# ADCMP607-step-gen-v2.net
KiCad netlist of a schematic drawn in EAGLE
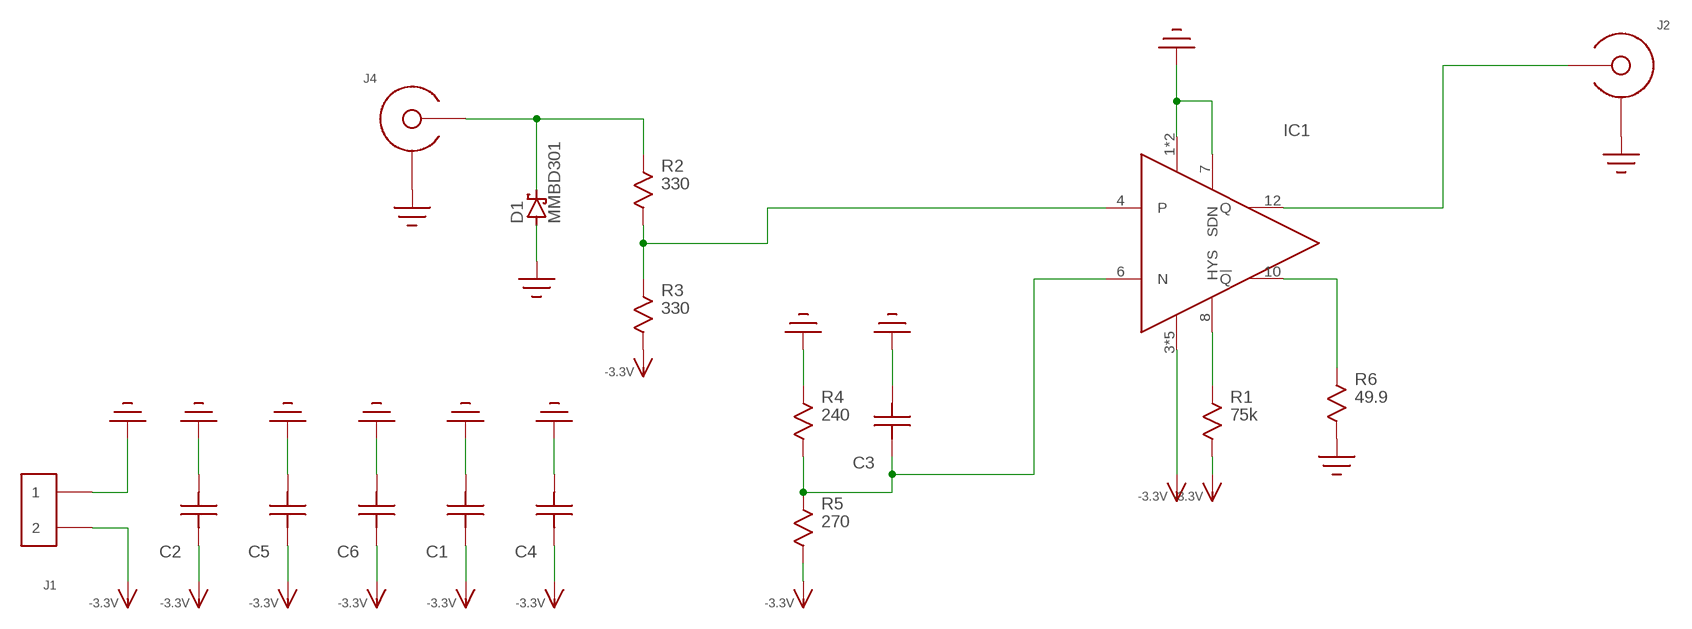
[diagram p0: schematic, sheet 1]

(export (version "E")
  (design (tool "Eeschema 10.0.6"))
  (components
    (comp (ref "C1")
      (value "C0603")
      (footprint "eagle-import:C0603")
      (libsource (lib "eagle-import") (part "C0603"))
    )
    (comp (ref "C2")
      (value "C1206")
      (footprint "eagle-import:1206")
      (libsource (lib "eagle-import") (part "C1206"))
    )
    (comp (ref "C3")
      (value "C0603")
      (footprint "eagle-import:C0603")
      (libsource (lib "eagle-import") (part "C0603"))
    )
    (comp (ref "C4")
      (value "C0603")
      (footprint "eagle-import:C0603")
      (libsource (lib "eagle-import") (part "C0603"))
    )
    (comp (ref "C5")
      (value "C0603")
      (footprint "eagle-import:C0603")
      (libsource (lib "eagle-import") (part "C0603"))
    )
    (comp (ref "C6")
      (value "C0603")
      (footprint "eagle-import:C0603")
      (libsource (lib "eagle-import") (part "C0603"))
    )
    (comp (ref "D1")
      (value "MMBD301")
      (footprint "eagle-import:SOT-23")
      (libsource (lib "eagle-import") (part "SCHOTTKY"))
    )
    (comp (ref "IC1")
      (value "ADCMP607")
      (footprint "eagle-import:QFN12-3X3")
      (libsource (lib "eagle-import") (part "ADCMP607"))
    )
    (comp (ref "J1")
      (value "HEADER_2PIN")
      (footprint "eagle-import:HEADER_2PIN")
      (libsource (lib "eagle-import") (part "HEADER_2PIN"))
    )
    (comp (ref "J2")
      (value "SMA-EDGE-LAUNCH4020_TAPER")
      (footprint "eagle-import:SMA_EDGE_LAUNCH_2L_4020_TAPER")
      (libsource (lib "eagle-import") (part "SMA-EDGE-LAUNCH4020_TAPER"))
    )
    (comp (ref "J4")
      (value "SMA-EDGE-LAUNCH4020_TAPER")
      (footprint "eagle-import:SMA_EDGE_LAUNCH_2L_4020_TAPER")
      (libsource (lib "eagle-import") (part "SMA-EDGE-LAUNCH4020_TAPER"))
    )
    (comp (ref "R1")
      (value "75k")
      (footprint "eagle-import:R0603")
      (libsource (lib "eagle-import") (part "R0603"))
    )
    (comp (ref "R2")
      (value "330")
      (footprint "eagle-import:R0603")
      (libsource (lib "eagle-import") (part "R0603"))
    )
    (comp (ref "R3")
      (value "330")
      (footprint "eagle-import:R0603")
      (libsource (lib "eagle-import") (part "R0603"))
    )
    (comp (ref "R4")
      (value "240")
      (footprint "eagle-import:R0603")
      (libsource (lib "eagle-import") (part "R0603"))
    )
    (comp (ref "R5")
      (value "270")
      (footprint "eagle-import:R0603")
      (libsource (lib "eagle-import") (part "R0603"))
    )
    (comp (ref "R6")
      (value "49.9")
      (footprint "eagle-import:R0603")
      (libsource (lib "eagle-import") (part "R0603"))
    )
  )
  (nets
    (net (code "1") (name "-3.3V") (class "Default")
      (node (ref "C1") (pin "P$2") (pinfunction "P$2_P$2") (pintype "bidirectional"))
      (node (ref "C2") (pin "P$2") (pinfunction "P$2_P$2") (pintype "bidirectional"))
      (node (ref "C4") (pin "P$2") (pinfunction "P$2_P$2") (pintype "bidirectional"))
      (node (ref "C5") (pin "P$2") (pinfunction "P$2_P$2") (pintype "bidirectional"))
      (node (ref "C6") (pin "P$2") (pinfunction "P$2_P$2") (pintype "bidirectional"))
      (node (ref "IC1") (pin "11") (pinfunction "VEE_11") (pintype "bidirectional"))
      (node (ref "IC1") (pin "3") (pinfunction "VEE_3") (pintype "bidirectional"))
      (node (ref "IC1") (pin "5") (pinfunction "VEE_5") (pintype "bidirectional"))
      (node (ref "IC1") (pin "9") (pinfunction "VEE_9") (pintype "bidirectional"))
      (node (ref "IC1") (pin "EP") (pinfunction "VEE_EP") (pintype "bidirectional"))
      (node (ref "J1") (pin "2") (pinfunction "2_2") (pintype "bidirectional"))
      (node (ref "R1") (pin "P$2") (pinfunction "P$4_P$2") (pintype "bidirectional"))
      (node (ref "R3") (pin "P$2") (pinfunction "P$4_P$2") (pintype "bidirectional"))
      (node (ref "R5") (pin "P$2") (pinfunction "P$4_P$2") (pintype "bidirectional"))
    )
    (net (code "2") (name "GND") (class "Default")
      (node (ref "C1") (pin "P$1") (pinfunction "P$1_P$1") (pintype "bidirectional"))
      (node (ref "C2") (pin "P$1") (pinfunction "P$1_P$1") (pintype "bidirectional"))
      (node (ref "C3") (pin "P$1") (pinfunction "P$1_P$1") (pintype "bidirectional"))
      (node (ref "C4") (pin "P$1") (pinfunction "P$1_P$1") (pintype "bidirectional"))
      (node (ref "C5") (pin "P$1") (pinfunction "P$1_P$1") (pintype "bidirectional"))
      (node (ref "C6") (pin "P$1") (pinfunction "P$1_P$1") (pintype "bidirectional"))
      (node (ref "D1") (pin "1") (pinfunction "A_1") (pintype "passive"))
      (node (ref "IC1") (pin "1") (pinfunction "VCC_1") (pintype "bidirectional"))
      (node (ref "IC1") (pin "2") (pinfunction "VCC_2") (pintype "bidirectional"))
      (node (ref "IC1") (pin "7") (pinfunction "SDN_7") (pintype "bidirectional"))
      (node (ref "J1") (pin "1") (pinfunction "1_1") (pintype "bidirectional"))
      (node (ref "J2") (pin "BOTTOM_GND") (pinfunction "SHIELD_BOTTOM_GND") (pintype "bidirectional"))
      (node (ref "J2") (pin "GND@1") (pinfunction "SHIELD_GND@1") (pintype "bidirectional"))
      (node (ref "J2") (pin "GND@14") (pinfunction "SHIELD_GND@14") (pintype "bidirectional"))
      (node (ref "J2") (pin "GND@15") (pinfunction "SHIELD_GND@15") (pintype "bidirectional"))
      (node (ref "J2") (pin "GND@16") (pinfunction "SHIELD_GND@16") (pintype "bidirectional"))
      (node (ref "J2") (pin "GND@17") (pinfunction "SHIELD_GND@17") (pintype "bidirectional"))
      (node (ref "J2") (pin "GND@2") (pinfunction "SHIELD_GND@2") (pintype "bidirectional"))
      (node (ref "J2") (pin "GND@3") (pinfunction "SHIELD_GND@3") (pintype "bidirectional"))
      (node (ref "J2") (pin "GND@4") (pinfunction "SHIELD_GND@4") (pintype "bidirectional"))
      (node (ref "J2") (pin "GND@5") (pinfunction "SHIELD_GND@5") (pintype "bidirectional"))
      (node (ref "J2") (pin "GND@6") (pinfunction "SHIELD_GND@6") (pintype "bidirectional"))
      (node (ref "J2") (pin "GND@7") (pinfunction "SHIELD_GND@7") (pintype "bidirectional"))
      (node (ref "J2") (pin "GND@8") (pinfunction "SHIELD_GND@8") (pintype "bidirectional"))
      (node (ref "J2") (pin "GND_PAD1") (pinfunction "SHIELD_GND_PAD1") (pintype "bidirectional"))
      (node (ref "J2") (pin "GND_PAD2") (pinfunction "SHIELD_GND_PAD2") (pintype "bidirectional"))
      (node (ref "J2") (pin "P$1") (pinfunction "SHIELD_P$1") (pintype "bidirectional"))
      (node (ref "J2") (pin "P$2") (pinfunction "SHIELD_P$2") (pintype "bidirectional"))
      (node (ref "J4") (pin "BOTTOM_GND") (pinfunction "SHIELD_BOTTOM_GND") (pintype "bidirectional"))
      (node (ref "J4") (pin "GND@1") (pinfunction "SHIELD_GND@1") (pintype "bidirectional"))
      (node (ref "J4") (pin "GND@14") (pinfunction "SHIELD_GND@14") (pintype "bidirectional"))
      (node (ref "J4") (pin "GND@15") (pinfunction "SHIELD_GND@15") (pintype "bidirectional"))
      (node (ref "J4") (pin "GND@16") (pinfunction "SHIELD_GND@16") (pintype "bidirectional"))
      (node (ref "J4") (pin "GND@17") (pinfunction "SHIELD_GND@17") (pintype "bidirectional"))
      (node (ref "J4") (pin "GND@2") (pinfunction "SHIELD_GND@2") (pintype "bidirectional"))
      (node (ref "J4") (pin "GND@3") (pinfunction "SHIELD_GND@3") (pintype "bidirectional"))
      (node (ref "J4") (pin "GND@4") (pinfunction "SHIELD_GND@4") (pintype "bidirectional"))
      (node (ref "J4") (pin "GND@5") (pinfunction "SHIELD_GND@5") (pintype "bidirectional"))
      (node (ref "J4") (pin "GND@6") (pinfunction "SHIELD_GND@6") (pintype "bidirectional"))
      (node (ref "J4") (pin "GND@7") (pinfunction "SHIELD_GND@7") (pintype "bidirectional"))
      (node (ref "J4") (pin "GND@8") (pinfunction "SHIELD_GND@8") (pintype "bidirectional"))
      (node (ref "J4") (pin "GND_PAD1") (pinfunction "SHIELD_GND_PAD1") (pintype "bidirectional"))
      (node (ref "J4") (pin "GND_PAD2") (pinfunction "SHIELD_GND_PAD2") (pintype "bidirectional"))
      (node (ref "J4") (pin "P$1") (pinfunction "SHIELD_P$1") (pintype "bidirectional"))
      (node (ref "J4") (pin "P$2") (pinfunction "SHIELD_P$2") (pintype "bidirectional"))
      (node (ref "R4") (pin "P$1") (pinfunction "P$3_P$1") (pintype "bidirectional"))
      (node (ref "R6") (pin "P$2") (pinfunction "P$4_P$2") (pintype "bidirectional"))
    )
    (net (code "3") (name "Net-(D1-C)") (class "Default")
      (node (ref "D1") (pin "3") (pinfunction "C_3") (pintype "passive"))
      (node (ref "J4") (pin "CENTER@1") (pinfunction "CENTER_CENTER@1") (pintype "bidirectional"))
      (node (ref "R2") (pin "P$1") (pinfunction "P$3_P$1") (pintype "bidirectional"))
    )
    (net (code "4") (name "Net-(IC1-HYS)") (class "Default")
      (node (ref "IC1") (pin "8") (pinfunction "HYS_8") (pintype "bidirectional"))
      (node (ref "R1") (pin "P$1") (pinfunction "P$3_P$1") (pintype "bidirectional"))
    )
    (net (code "5") (name "Net-(IC1-N)") (class "Default")
      (node (ref "C3") (pin "P$2") (pinfunction "P$2_P$2") (pintype "bidirectional"))
      (node (ref "IC1") (pin "6") (pinfunction "N_6") (pintype "bidirectional"))
      (node (ref "R4") (pin "P$2") (pinfunction "P$4_P$2") (pintype "bidirectional"))
      (node (ref "R5") (pin "P$1") (pinfunction "P$3_P$1") (pintype "bidirectional"))
    )
    (net (code "6") (name "Net-(IC1-P)") (class "Default")
      (node (ref "IC1") (pin "4") (pinfunction "P_4") (pintype "bidirectional"))
      (node (ref "R2") (pin "P$2") (pinfunction "P$4_P$2") (pintype "bidirectional"))
      (node (ref "R3") (pin "P$1") (pinfunction "P$3_P$1") (pintype "bidirectional"))
    )
    (net (code "7") (name "Net-(IC1-Q)") (class "Default")
      (node (ref "IC1") (pin "12") (pinfunction "Q_12") (pintype "bidirectional"))
      (node (ref "J2") (pin "CENTER@1") (pinfunction "CENTER_CENTER@1") (pintype "bidirectional"))
    )
    (net (code "8") (name "Net-(IC1-~{Q})") (class "Default")
      (node (ref "IC1") (pin "10") (pinfunction "~{Q}_10") (pintype "bidirectional"))
      (node (ref "R6") (pin "P$1") (pinfunction "P$3_P$1") (pintype "bidirectional"))
    )
  )
)
